# LT3465Breakout.net
KiCad netlist of a schematic drawn in EAGLE
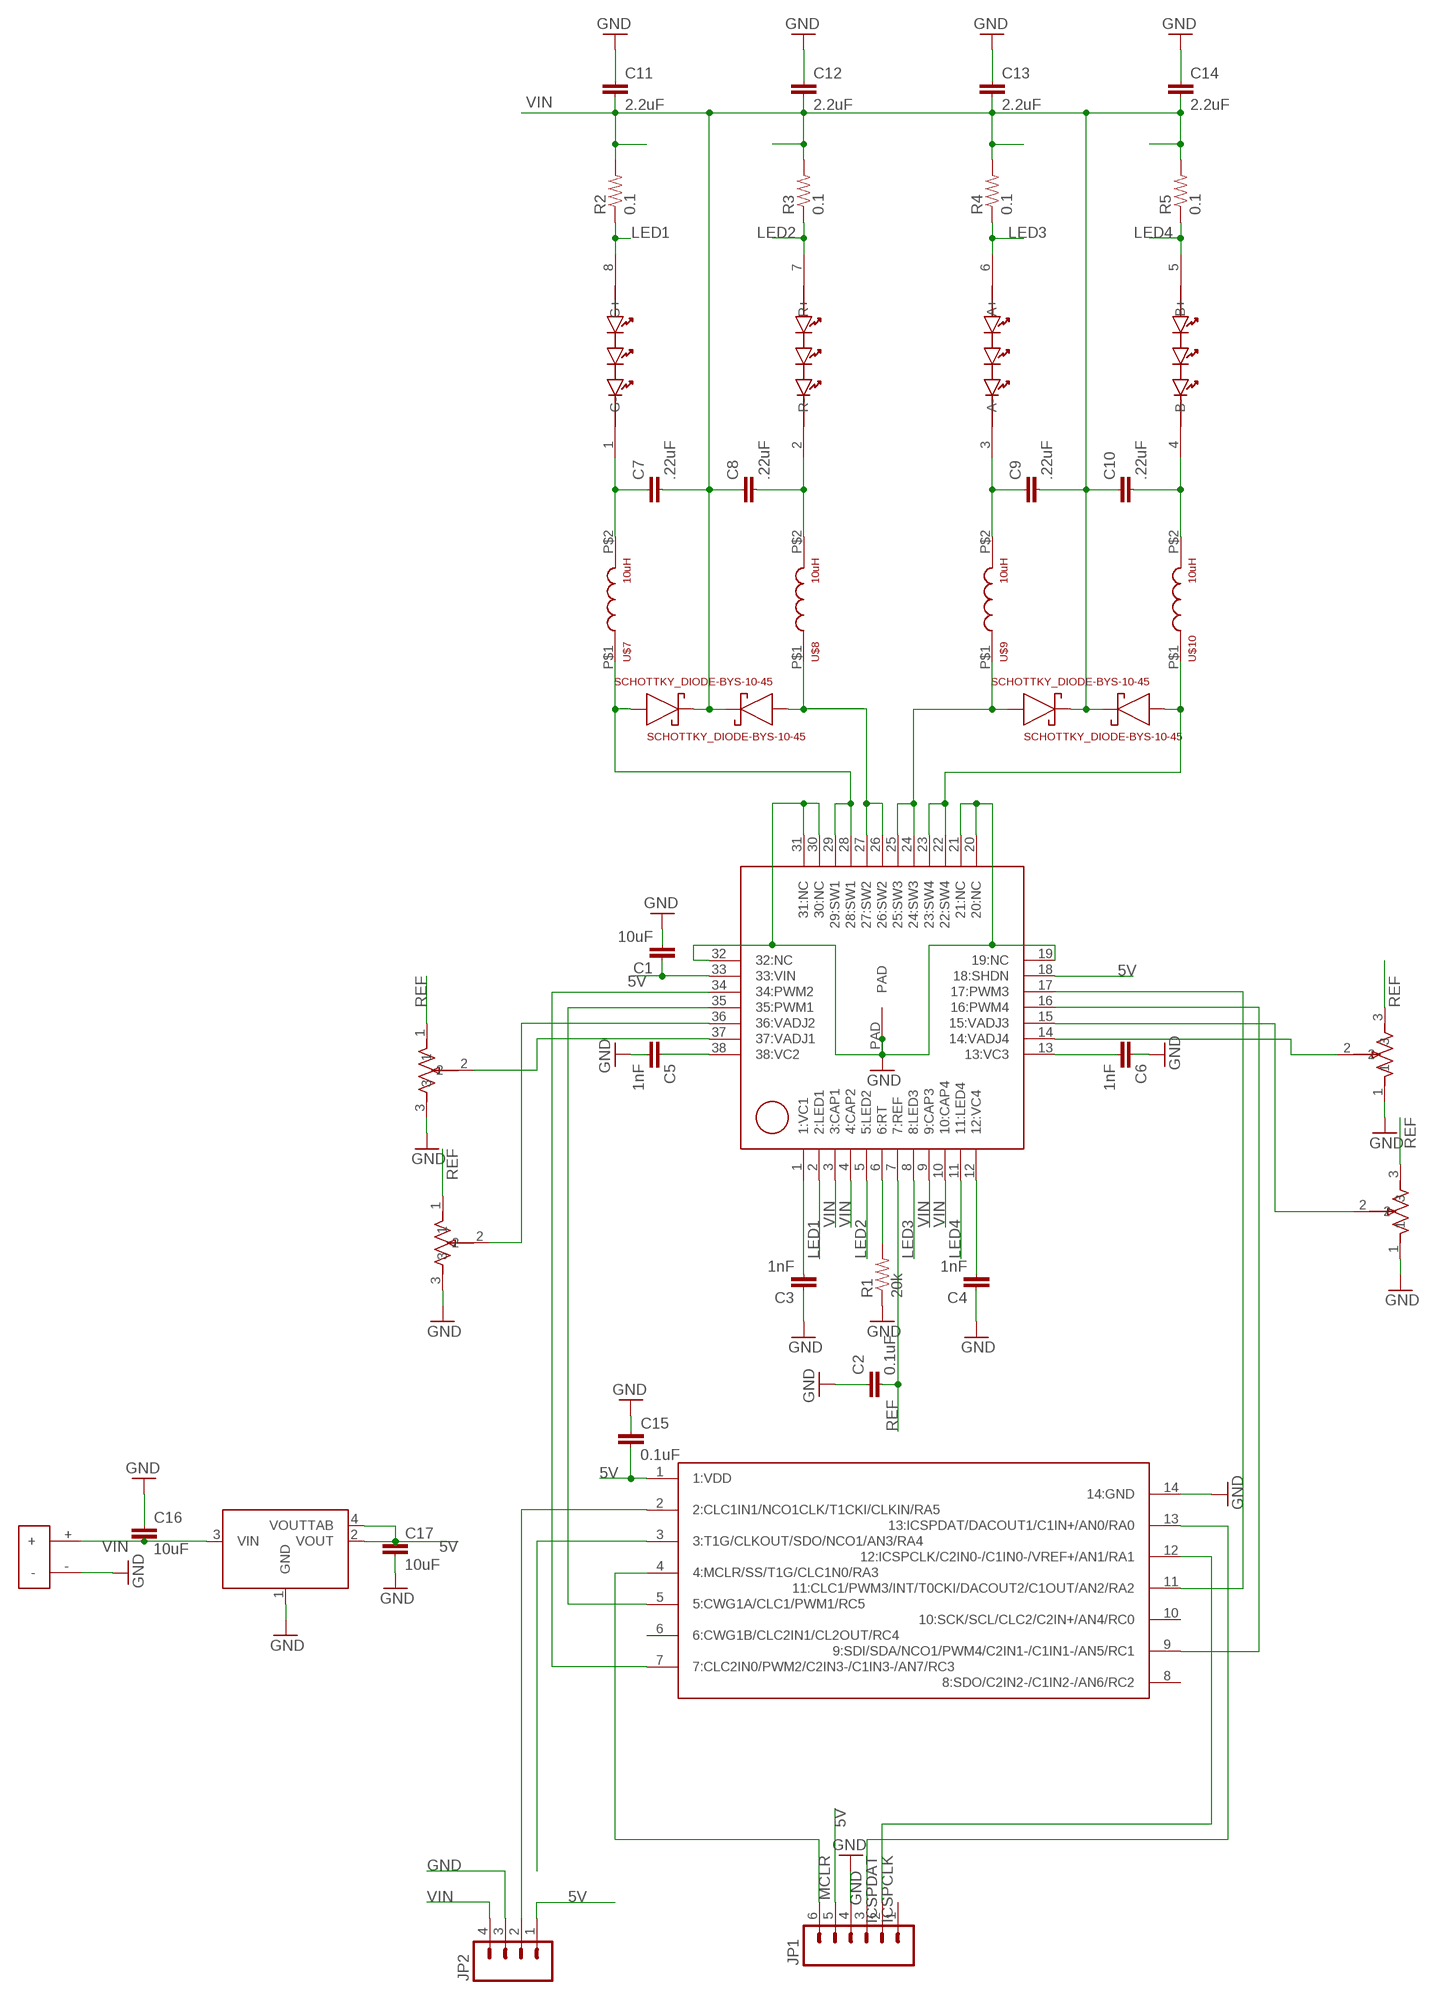
[diagram p0: schematic, sheet 1]

(export (version "E")
  (design (tool "Eeschema 10.0.6"))
  (components
    (comp (ref "C1")
      (value "10uF")
      (footprint "eagle-import:1210")
      (libsource (lib "eagle-import") (part "CAP1210"))
    )
    (comp (ref "C2")
      (value "0.1uF")
      (footprint "eagle-import:0805")
      (libsource (lib "eagle-import") (part "CAP0805"))
    )
    (comp (ref "C3")
      (value "1nF")
      (footprint "eagle-import:0805")
      (libsource (lib "eagle-import") (part "CAP0805"))
    )
    (comp (ref "C4")
      (value "1nF")
      (footprint "eagle-import:0805")
      (libsource (lib "eagle-import") (part "CAP0805"))
    )
    (comp (ref "C5")
      (value "1nF")
      (footprint "eagle-import:0805")
      (libsource (lib "eagle-import") (part "CAP0805"))
    )
    (comp (ref "C6")
      (value "1nF")
      (footprint "eagle-import:0805")
      (libsource (lib "eagle-import") (part "CAP0805"))
    )
    (comp (ref "C7")
      (value ".22uF")
      (footprint "eagle-import:0805")
      (libsource (lib "eagle-import") (part "CAP0805"))
    )
    (comp (ref "C8")
      (value ".22uF")
      (footprint "eagle-import:0805")
      (libsource (lib "eagle-import") (part "CAP0805"))
    )
    (comp (ref "C9")
      (value ".22uF")
      (footprint "eagle-import:0805")
      (libsource (lib "eagle-import") (part "CAP0805"))
    )
    (comp (ref "C10")
      (value ".22uF")
      (footprint "eagle-import:0805")
      (libsource (lib "eagle-import") (part "CAP0805"))
    )
    (comp (ref "C11")
      (value "2.2uF")
      (footprint "eagle-import:1206")
      (libsource (lib "eagle-import") (part "CAP1206"))
    )
    (comp (ref "C12")
      (value "2.2uF")
      (footprint "eagle-import:1206")
      (libsource (lib "eagle-import") (part "CAP1206"))
    )
    (comp (ref "C13")
      (value "2.2uF")
      (footprint "eagle-import:1206")
      (libsource (lib "eagle-import") (part "CAP1206"))
    )
    (comp (ref "C14")
      (value "2.2uF")
      (footprint "eagle-import:1206")
      (libsource (lib "eagle-import") (part "CAP1206"))
    )
    (comp (ref "C15")
      (value "0.1uF")
      (footprint "eagle-import:0805")
      (libsource (lib "eagle-import") (part "CAP0805"))
    )
    (comp (ref "C16")
      (value "10uF")
      (footprint "eagle-import:1206")
      (libsource (lib "eagle-import") (part "CAP1206"))
    )
    (comp (ref "C17")
      (value "10uF")
      (footprint "eagle-import:1206")
      (libsource (lib "eagle-import") (part "CAP1206"))
    )
    (comp (ref "JP1")
      (value "M06LOCK")
      (footprint "eagle-import:1X06_LOCK")
      (libsource (lib "eagle-import") (part "M06LOCK"))
    )
    (comp (ref "JP2")
      (value "M04LOCK")
      (footprint "eagle-import:1X04_LOCK")
      (libsource (lib "eagle-import") (part "M04LOCK"))
    )
    (comp (ref "R1")
      (value "20k")
      (footprint "eagle-import:0805")
      (libsource (lib "eagle-import") (part "RESISTOR"))
    )
    (comp (ref "R2")
      (value "0.1")
      (footprint "eagle-import:1206")
      (libsource (lib "eagle-import") (part "RESISTOR1206"))
    )
    (comp (ref "R3")
      (value "0.1")
      (footprint "eagle-import:1206")
      (libsource (lib "eagle-import") (part "RESISTOR1206"))
    )
    (comp (ref "R4")
      (value "0.1")
      (footprint "eagle-import:1206")
      (libsource (lib "eagle-import") (part "RESISTOR1206"))
    )
    (comp (ref "R5")
      (value "0.1")
      (footprint "eagle-import:1206")
      (libsource (lib "eagle-import") (part "RESISTOR1206"))
    )
    (comp (ref "U$1")
      (value "LT3476")
      (footprint "eagle-import:QFN-38")
      (libsource (lib "eagle-import") (part "LT3476"))
    )
    (comp (ref "U$2")
      (value "PIC16F1503TSSOP14")
      (footprint "eagle-import:TSSOP14")
      (libsource (lib "eagle-import") (part "PIC16F1503TSSOP14"))
    )
    (comp (ref "U$3")
      (value "SCHOTTKY_DIODE-BYS-10-45")
      (footprint "eagle-import:DO-214")
      (libsource (lib "eagle-import") (part "SCHOTTKY_DIODE-BYS-10-45"))
    )
    (comp (ref "U$4")
      (value "SCHOTTKY_DIODE-BYS-10-45")
      (footprint "eagle-import:DO-214")
      (libsource (lib "eagle-import") (part "SCHOTTKY_DIODE-BYS-10-45"))
    )
    (comp (ref "U$5")
      (value "SCHOTTKY_DIODE-BYS-10-45")
      (footprint "eagle-import:DO-214")
      (libsource (lib "eagle-import") (part "SCHOTTKY_DIODE-BYS-10-45"))
    )
    (comp (ref "U$6")
      (value "SCHOTTKY_DIODE-BYS-10-45")
      (footprint "eagle-import:DO-214")
      (libsource (lib "eagle-import") (part "SCHOTTKY_DIODE-BYS-10-45"))
    )
    (comp (ref "U$7")
      (value "10uH")
      (footprint "eagle-import:LQH88")
      (libsource (lib "eagle-import") (part "INDUCTOR-LQH88"))
    )
    (comp (ref "U$8")
      (value "10uH")
      (footprint "eagle-import:LQH88")
      (libsource (lib "eagle-import") (part "INDUCTOR-LQH88"))
    )
    (comp (ref "U$9")
      (value "10uH")
      (footprint "eagle-import:LQH88")
      (libsource (lib "eagle-import") (part "INDUCTOR-LQH88"))
    )
    (comp (ref "U$10")
      (value "10uH")
      (footprint "eagle-import:LQH88")
      (libsource (lib "eagle-import") (part "INDUCTOR-LQH88"))
    )
    (comp (ref "U$11")
      (value "LZC-00-MA00")
      (footprint "eagle-import:LZC-00MA00")
      (libsource (lib "eagle-import") (part "LZC-00-MA00"))
    )
    (comp (ref "U$12")
      (value "TRIMPOTTC33X-2")
      (footprint "eagle-import:TC33X-2")
      (libsource (lib "eagle-import") (part "TRIMPOTTC33X-2"))
    )
    (comp (ref "U$13")
      (value "TRIMPOTTC33X-2")
      (footprint "eagle-import:TC33X-2")
      (libsource (lib "eagle-import") (part "TRIMPOTTC33X-2"))
    )
    (comp (ref "U$14")
      (value "TRIMPOTTC33X-2")
      (footprint "eagle-import:TC33X-2")
      (libsource (lib "eagle-import") (part "TRIMPOTTC33X-2"))
    )
    (comp (ref "U$15")
      (value "TRIMPOTTC33X-2")
      (footprint "eagle-import:TC33X-2")
      (libsource (lib "eagle-import") (part "TRIMPOTTC33X-2"))
    )
    (comp (ref "U$16")
      (value "5V-LDO-ZLDO1117")
      (footprint "eagle-import:ZLDO1117")
      (libsource (lib "eagle-import") (part "5V-LDO-ZLDO1117"))
    )
    (comp (ref "U$17")
      (value "POWER_SOLDER-1.5")
      (footprint "eagle-import:POWER_SOLDER")
      (libsource (lib "eagle-import") (part "POWER_SOLDER-1.5"))
    )
  )
  (nets
    (net (code "1") (name "/5V") (class "Default")
      (node (ref "C1") (pin "1") (pinfunction "1_1") (pintype "passive"))
      (node (ref "C15") (pin "2") (pinfunction "2_2") (pintype "passive"))
      (node (ref "C17") (pin "1") (pinfunction "1_1") (pintype "passive"))
      (node (ref "JP1") (pin "5") (pinfunction "5_5") (pintype "passive"))
      (node (ref "JP2") (pin "1") (pinfunction "1_1") (pintype "passive"))
      (node (ref "U$1") (pin "18") (pinfunction "18:SHDN_18") (pintype "bidirectional"))
      (node (ref "U$1") (pin "33") (pinfunction "33:VIN_33") (pintype "bidirectional"))
      (node (ref "U$16") (pin "2") (pinfunction "VOUT_2") (pintype "bidirectional"))
      (node (ref "U$16") (pin "4") (pinfunction "VOUTTAB_4") (pintype "bidirectional"))
      (node (ref "U$2") (pin "1") (pinfunction "1:VDD_1") (pintype "bidirectional"))
    )
    (net (code "2") (name "/ICSPCLK") (class "Default")
      (node (ref "JP1") (pin "2") (pinfunction "2_2") (pintype "passive"))
      (node (ref "U$2") (pin "12") (pinfunction "12:ICSPCLK/C2IN0-/C1IN0-/VREF+/AN1/RA1_12") (pintype "bidirectional"))
    )
    (net (code "3") (name "/ICSPDAT") (class "Default")
      (node (ref "JP1") (pin "3") (pinfunction "3_3") (pintype "passive"))
      (node (ref "U$2") (pin "13") (pinfunction "13:ICSPDAT/DACOUT1/C1IN+/AN0/RA0_13") (pintype "bidirectional"))
    )
    (net (code "4") (name "/LED1") (class "Default")
      (node (ref "R2") (pin "1") (pinfunction "1_1") (pintype "passive"))
      (node (ref "U$1") (pin "2") (pinfunction "2:LED1_2") (pintype "bidirectional"))
      (node (ref "U$11") (pin "8") (pinfunction "G+_8") (pintype "bidirectional"))
    )
    (net (code "5") (name "/LED2") (class "Default")
      (node (ref "R3") (pin "1") (pinfunction "1_1") (pintype "passive"))
      (node (ref "U$1") (pin "5") (pinfunction "5:LED2_5") (pintype "bidirectional"))
      (node (ref "U$11") (pin "7") (pinfunction "R+_7") (pintype "bidirectional"))
    )
    (net (code "6") (name "/LED3") (class "Default")
      (node (ref "R4") (pin "1") (pinfunction "1_1") (pintype "passive"))
      (node (ref "U$1") (pin "8") (pinfunction "8:LED3_8") (pintype "bidirectional"))
      (node (ref "U$11") (pin "6") (pinfunction "A+_6") (pintype "bidirectional"))
    )
    (net (code "7") (name "/LED4") (class "Default")
      (node (ref "R5") (pin "1") (pinfunction "1_1") (pintype "passive"))
      (node (ref "U$1") (pin "11") (pinfunction "11:LED4_11") (pintype "bidirectional"))
      (node (ref "U$11") (pin "5") (pinfunction "B+_5") (pintype "bidirectional"))
    )
    (net (code "8") (name "/MCLR") (class "Default")
      (node (ref "JP1") (pin "6") (pinfunction "6_6") (pintype "passive"))
      (node (ref "U$2") (pin "4") (pinfunction "4:MCLR/SS/T1G/CLC1N0/RA3_4") (pintype "bidirectional"))
    )
    (net (code "9") (name "/REF") (class "Default")
      (node (ref "C2") (pin "2") (pinfunction "2_2") (pintype "passive"))
      (node (ref "U$1") (pin "7") (pinfunction "7:REF_7") (pintype "bidirectional"))
      (node (ref "U$12") (pin "1") (pinfunction "1_1") (pintype "bidirectional"))
      (node (ref "U$13") (pin "1") (pinfunction "1_1") (pintype "bidirectional"))
      (node (ref "U$14") (pin "3") (pinfunction "3_3") (pintype "bidirectional"))
      (node (ref "U$15") (pin "3") (pinfunction "3_3") (pintype "bidirectional"))
    )
    (net (code "10") (name "/VIN") (class "Default")
      (node (ref "C10") (pin "1") (pinfunction "1_1") (pintype "passive"))
      (node (ref "C11") (pin "2") (pinfunction "2_2") (pintype "passive"))
      (node (ref "C12") (pin "2") (pinfunction "2_2") (pintype "passive"))
      (node (ref "C13") (pin "2") (pinfunction "2_2") (pintype "passive"))
      (node (ref "C14") (pin "2") (pinfunction "2_2") (pintype "passive"))
      (node (ref "C16") (pin "2") (pinfunction "2_2") (pintype "passive"))
      (node (ref "C7") (pin "2") (pinfunction "2_2") (pintype "passive"))
      (node (ref "C8") (pin "1") (pinfunction "1_1") (pintype "passive"))
      (node (ref "C9") (pin "2") (pinfunction "2_2") (pintype "passive"))
      (node (ref "JP2") (pin "4") (pinfunction "4_4") (pintype "passive"))
      (node (ref "R2") (pin "2") (pinfunction "2_2") (pintype "passive"))
      (node (ref "R3") (pin "2") (pinfunction "2_2") (pintype "passive"))
      (node (ref "R4") (pin "2") (pinfunction "2_2") (pintype "passive"))
      (node (ref "R5") (pin "2") (pinfunction "2_2") (pintype "passive"))
      (node (ref "U$1") (pin "10") (pinfunction "10:CAP4_10") (pintype "bidirectional"))
      (node (ref "U$1") (pin "3") (pinfunction "3:CAP1_3") (pintype "bidirectional"))
      (node (ref "U$1") (pin "4") (pinfunction "4:CAP2_4") (pintype "bidirectional"))
      (node (ref "U$1") (pin "9") (pinfunction "9:CAP3_9") (pintype "bidirectional"))
      (node (ref "U$16") (pin "3") (pinfunction "VIN_3") (pintype "bidirectional"))
      (node (ref "U$17") (pin "+") (pinfunction "+_+") (pintype "bidirectional"))
      (node (ref "U$3") (pin "P$1") (pinfunction "CATHODE_P$1") (pintype "bidirectional"))
      (node (ref "U$4") (pin "P$1") (pinfunction "CATHODE_P$1") (pintype "bidirectional"))
      (node (ref "U$5") (pin "P$1") (pinfunction "CATHODE_P$1") (pintype "bidirectional"))
      (node (ref "U$6") (pin "P$1") (pinfunction "CATHODE_P$1") (pintype "bidirectional"))
    )
    (net (code "11") (name "GND") (class "Default")
      (node (ref "C1") (pin "2") (pinfunction "2_2") (pintype "passive"))
      (node (ref "C11") (pin "1") (pinfunction "1_1") (pintype "passive"))
      (node (ref "C12") (pin "1") (pinfunction "1_1") (pintype "passive"))
      (node (ref "C13") (pin "1") (pinfunction "1_1") (pintype "passive"))
      (node (ref "C14") (pin "1") (pinfunction "1_1") (pintype "passive"))
      (node (ref "C15") (pin "1") (pinfunction "1_1") (pintype "passive"))
      (node (ref "C16") (pin "1") (pinfunction "1_1") (pintype "passive"))
      (node (ref "C17") (pin "2") (pinfunction "2_2") (pintype "passive"))
      (node (ref "C2") (pin "1") (pinfunction "1_1") (pintype "passive"))
      (node (ref "C3") (pin "1") (pinfunction "1_1") (pintype "passive"))
      (node (ref "C4") (pin "1") (pinfunction "1_1") (pintype "passive"))
      (node (ref "C5") (pin "2") (pinfunction "2_2") (pintype "passive"))
      (node (ref "C6") (pin "1") (pinfunction "1_1") (pintype "passive"))
      (node (ref "JP1") (pin "4") (pinfunction "4_4") (pintype "passive"))
      (node (ref "JP2") (pin "3") (pinfunction "3_3") (pintype "passive"))
      (node (ref "R1") (pin "1") (pinfunction "1_1") (pintype "passive"))
      (node (ref "U$1") (pin "19") (pinfunction "19:NC_19") (pintype "bidirectional"))
      (node (ref "U$1") (pin "20") (pinfunction "20:NC_20") (pintype "bidirectional"))
      (node (ref "U$1") (pin "21") (pinfunction "21:NC_21") (pintype "bidirectional"))
      (node (ref "U$1") (pin "30") (pinfunction "30:NC_30") (pintype "bidirectional"))
      (node (ref "U$1") (pin "31") (pinfunction "31:NC_31") (pintype "bidirectional"))
      (node (ref "U$1") (pin "32") (pinfunction "32:NC_32") (pintype "bidirectional"))
      (node (ref "U$1") (pin "PAD") (pinfunction "PAD_PAD") (pintype "bidirectional"))
      (node (ref "U$12") (pin "3") (pinfunction "3_3") (pintype "bidirectional"))
      (node (ref "U$13") (pin "3") (pinfunction "3_3") (pintype "bidirectional"))
      (node (ref "U$14") (pin "1") (pinfunction "1_1") (pintype "bidirectional"))
      (node (ref "U$15") (pin "1") (pinfunction "1_1") (pintype "bidirectional"))
      (node (ref "U$16") (pin "1") (pinfunction "GND_1") (pintype "bidirectional"))
      (node (ref "U$17") (pin "-") (pinfunction "-_-") (pintype "bidirectional"))
      (node (ref "U$2") (pin "14") (pinfunction "14:GND_14") (pintype "bidirectional"))
    )
    (net (code "12") (name "Net-(U$1-1:VC1)") (class "Default")
      (node (ref "C3") (pin "2") (pinfunction "2_2") (pintype "passive"))
      (node (ref "U$1") (pin "1") (pinfunction "1:VC1_1") (pintype "bidirectional"))
    )
    (net (code "13") (name "Net-(U$1-6:RT)") (class "Default")
      (node (ref "R1") (pin "2") (pinfunction "2_2") (pintype "passive"))
      (node (ref "U$1") (pin "6") (pinfunction "6:RT_6") (pintype "bidirectional"))
    )
    (net (code "14") (name "Net-(U$1-12:VC4)") (class "Default")
      (node (ref "C4") (pin "2") (pinfunction "2_2") (pintype "passive"))
      (node (ref "U$1") (pin "12") (pinfunction "12:VC4_12") (pintype "bidirectional"))
    )
    (net (code "15") (name "Net-(U$1-13:VC3)") (class "Default")
      (node (ref "C6") (pin "2") (pinfunction "2_2") (pintype "passive"))
      (node (ref "U$1") (pin "13") (pinfunction "13:VC3_13") (pintype "bidirectional"))
    )
    (net (code "16") (name "Net-(U$1-14:VADJ4)") (class "Default")
      (node (ref "U$1") (pin "14") (pinfunction "14:VADJ4_14") (pintype "bidirectional"))
      (node (ref "U$14") (pin "2") (pinfunction "2_2") (pintype "bidirectional"))
    )
    (net (code "17") (name "Net-(U$1-15:VADJ3)") (class "Default")
      (node (ref "U$1") (pin "15") (pinfunction "15:VADJ3_15") (pintype "bidirectional"))
      (node (ref "U$15") (pin "2") (pinfunction "2_2") (pintype "bidirectional"))
    )
    (net (code "18") (name "Net-(U$1-16:PWM4)") (class "Default")
      (node (ref "U$1") (pin "16") (pinfunction "16:PWM4_16") (pintype "bidirectional"))
      (node (ref "U$2") (pin "9") (pinfunction "9:SDI/SDA/NCO1/PWM4/C2IN1-/C1IN1-/AN5/RC1_9") (pintype "bidirectional"))
    )
    (net (code "19") (name "Net-(U$1-17:PWM3)") (class "Default")
      (node (ref "U$1") (pin "17") (pinfunction "17:PWM3_17") (pintype "bidirectional"))
      (node (ref "U$2") (pin "11") (pinfunction "11:CLC1/PWM3/INT/T0CKI/DACOUT2/C1OUT/AN2/RA2_11") (pintype "bidirectional"))
    )
    (net (code "20") (name "Net-(U$1-22:SW4)") (class "Default")
      (node (ref "U$1") (pin "22") (pinfunction "22:SW4_22") (pintype "bidirectional"))
      (node (ref "U$1") (pin "23") (pinfunction "23:SW4_23") (pintype "bidirectional"))
      (node (ref "U$10") (pin "P$1") (pinfunction "P$1_P$1") (pintype "bidirectional"))
      (node (ref "U$6") (pin "P$2") (pinfunction "ANODE_P$2") (pintype "bidirectional"))
    )
    (net (code "21") (name "Net-(U$1-24:SW3)") (class "Default")
      (node (ref "U$1") (pin "24") (pinfunction "24:SW3_24") (pintype "bidirectional"))
      (node (ref "U$1") (pin "25") (pinfunction "25:SW3_25") (pintype "bidirectional"))
      (node (ref "U$5") (pin "P$2") (pinfunction "ANODE_P$2") (pintype "bidirectional"))
      (node (ref "U$9") (pin "P$1") (pinfunction "P$1_P$1") (pintype "bidirectional"))
    )
    (net (code "22") (name "Net-(U$1-26:SW2)") (class "Default")
      (node (ref "U$1") (pin "26") (pinfunction "26:SW2_26") (pintype "bidirectional"))
      (node (ref "U$1") (pin "27") (pinfunction "27:SW2_27") (pintype "bidirectional"))
      (node (ref "U$4") (pin "P$2") (pinfunction "ANODE_P$2") (pintype "bidirectional"))
      (node (ref "U$8") (pin "P$1") (pinfunction "P$1_P$1") (pintype "bidirectional"))
    )
    (net (code "23") (name "Net-(U$1-28:SW1)") (class "Default")
      (node (ref "U$1") (pin "28") (pinfunction "28:SW1_28") (pintype "bidirectional"))
      (node (ref "U$1") (pin "29") (pinfunction "29:SW1_29") (pintype "bidirectional"))
      (node (ref "U$3") (pin "P$2") (pinfunction "ANODE_P$2") (pintype "bidirectional"))
      (node (ref "U$7") (pin "P$1") (pinfunction "P$1_P$1") (pintype "bidirectional"))
    )
    (net (code "24") (name "Net-(U$1-34:PWM2)") (class "Default")
      (node (ref "U$1") (pin "34") (pinfunction "34:PWM2_34") (pintype "bidirectional"))
      (node (ref "U$2") (pin "7") (pinfunction "7:CLC2IN0/PWM2/C2IN3-/C1IN3-/AN7/RC3_7") (pintype "bidirectional"))
    )
    (net (code "25") (name "Net-(U$1-35:PWM1)") (class "Default")
      (node (ref "U$1") (pin "35") (pinfunction "35:PWM1_35") (pintype "bidirectional"))
      (node (ref "U$2") (pin "5") (pinfunction "5:CWG1A/CLC1/PWM1/RC5_5") (pintype "bidirectional"))
    )
    (net (code "26") (name "Net-(U$1-36:VADJ2)") (class "Default")
      (node (ref "U$1") (pin "36") (pinfunction "36:VADJ2_36") (pintype "bidirectional"))
      (node (ref "U$13") (pin "2") (pinfunction "2_2") (pintype "bidirectional"))
    )
    (net (code "27") (name "Net-(U$1-37:VADJ1)") (class "Default")
      (node (ref "U$1") (pin "37") (pinfunction "37:VADJ1_37") (pintype "bidirectional"))
      (node (ref "U$12") (pin "2") (pinfunction "2_2") (pintype "bidirectional"))
    )
    (net (code "28") (name "Net-(U$1-38:VC2)") (class "Default")
      (node (ref "C5") (pin "1") (pinfunction "1_1") (pintype "passive"))
      (node (ref "U$1") (pin "38") (pinfunction "38:VC2_38") (pintype "bidirectional"))
    )
    (net (code "29") (name "Net-(U$2-2:CLC1IN1{slash}NCO1CLK{slash}T1CKI{slash}CLKIN{slash}RA5)") (class "Default")
      (node (ref "JP2") (pin "2") (pinfunction "2_2") (pintype "passive"))
      (node (ref "U$2") (pin "2") (pinfunction "2:CLC1IN1/NCO1CLK/T1CKI/CLKIN/RA5_2") (pintype "bidirectional"))
    )
    (net (code "30") (name "Net-(U$11-A-)") (class "Default")
      (node (ref "C9") (pin "1") (pinfunction "1_1") (pintype "passive"))
      (node (ref "U$11") (pin "3") (pinfunction "A-_3") (pintype "bidirectional"))
      (node (ref "U$9") (pin "P$2") (pinfunction "P$2_P$2") (pintype "bidirectional"))
    )
    (net (code "31") (name "Net-(U$11-B-)") (class "Default")
      (node (ref "C10") (pin "2") (pinfunction "2_2") (pintype "passive"))
      (node (ref "U$10") (pin "P$2") (pinfunction "P$2_P$2") (pintype "bidirectional"))
      (node (ref "U$11") (pin "4") (pinfunction "B-_4") (pintype "bidirectional"))
    )
    (net (code "32") (name "Net-(U$11-G-)") (class "Default")
      (node (ref "C7") (pin "1") (pinfunction "1_1") (pintype "passive"))
      (node (ref "U$11") (pin "1") (pinfunction "G-_1") (pintype "bidirectional"))
      (node (ref "U$7") (pin "P$2") (pinfunction "P$2_P$2") (pintype "bidirectional"))
    )
    (net (code "33") (name "Net-(U$11-R-)") (class "Default")
      (node (ref "C8") (pin "2") (pinfunction "2_2") (pintype "passive"))
      (node (ref "U$11") (pin "2") (pinfunction "R-_2") (pintype "bidirectional"))
      (node (ref "U$8") (pin "P$2") (pinfunction "P$2_P$2") (pintype "bidirectional"))
    )
    (net (code "34") (name "unconnected-(JP1-Pad1)") (class "Default")
      (node (ref "JP1") (pin "1") (pinfunction "1_1") (pintype "passive"))
    )
    (net (code "35") (name "unconnected-(U$2-3:T1G{slash}CLKOUT{slash}SDO{slash}NCO1{slash}AN3{slash}RA4-Pad3)") (class "Default")
      (node (ref "U$2") (pin "3") (pinfunction "3:T1G/CLKOUT/SDO/NCO1/AN3/RA4_3") (pintype "bidirectional"))
    )
    (net (code "36") (name "unconnected-(U$2-6:CWG1B{slash}CLC2IN1{slash}CL2OUT{slash}RC4-Pad6)") (class "Default")
      (node (ref "U$2") (pin "6") (pinfunction "6:CWG1B/CLC2IN1/CL2OUT/RC4_6") (pintype "bidirectional"))
    )
    (net (code "37") (name "unconnected-(U$2-8:SDO{slash}C2IN2-{slash}C1IN2-{slash}AN6{slash}RC2-Pad8)") (class "Default")
      (node (ref "U$2") (pin "8") (pinfunction "8:SDO/C2IN2-/C1IN2-/AN6/RC2_8") (pintype "bidirectional"))
    )
    (net (code "38") (name "unconnected-(U$2-10:SCK{slash}SCL{slash}CLC2{slash}C2IN+{slash}AN4{slash}RC0-Pad10)") (class "Default")
      (node (ref "U$2") (pin "10") (pinfunction "10:SCK/SCL/CLC2/C2IN+/AN4/RC0_10") (pintype "bidirectional"))
    )
  )
)
